# AirQualityMonitor.net
KiCad netlist of a schematic drawn in Altium Designer
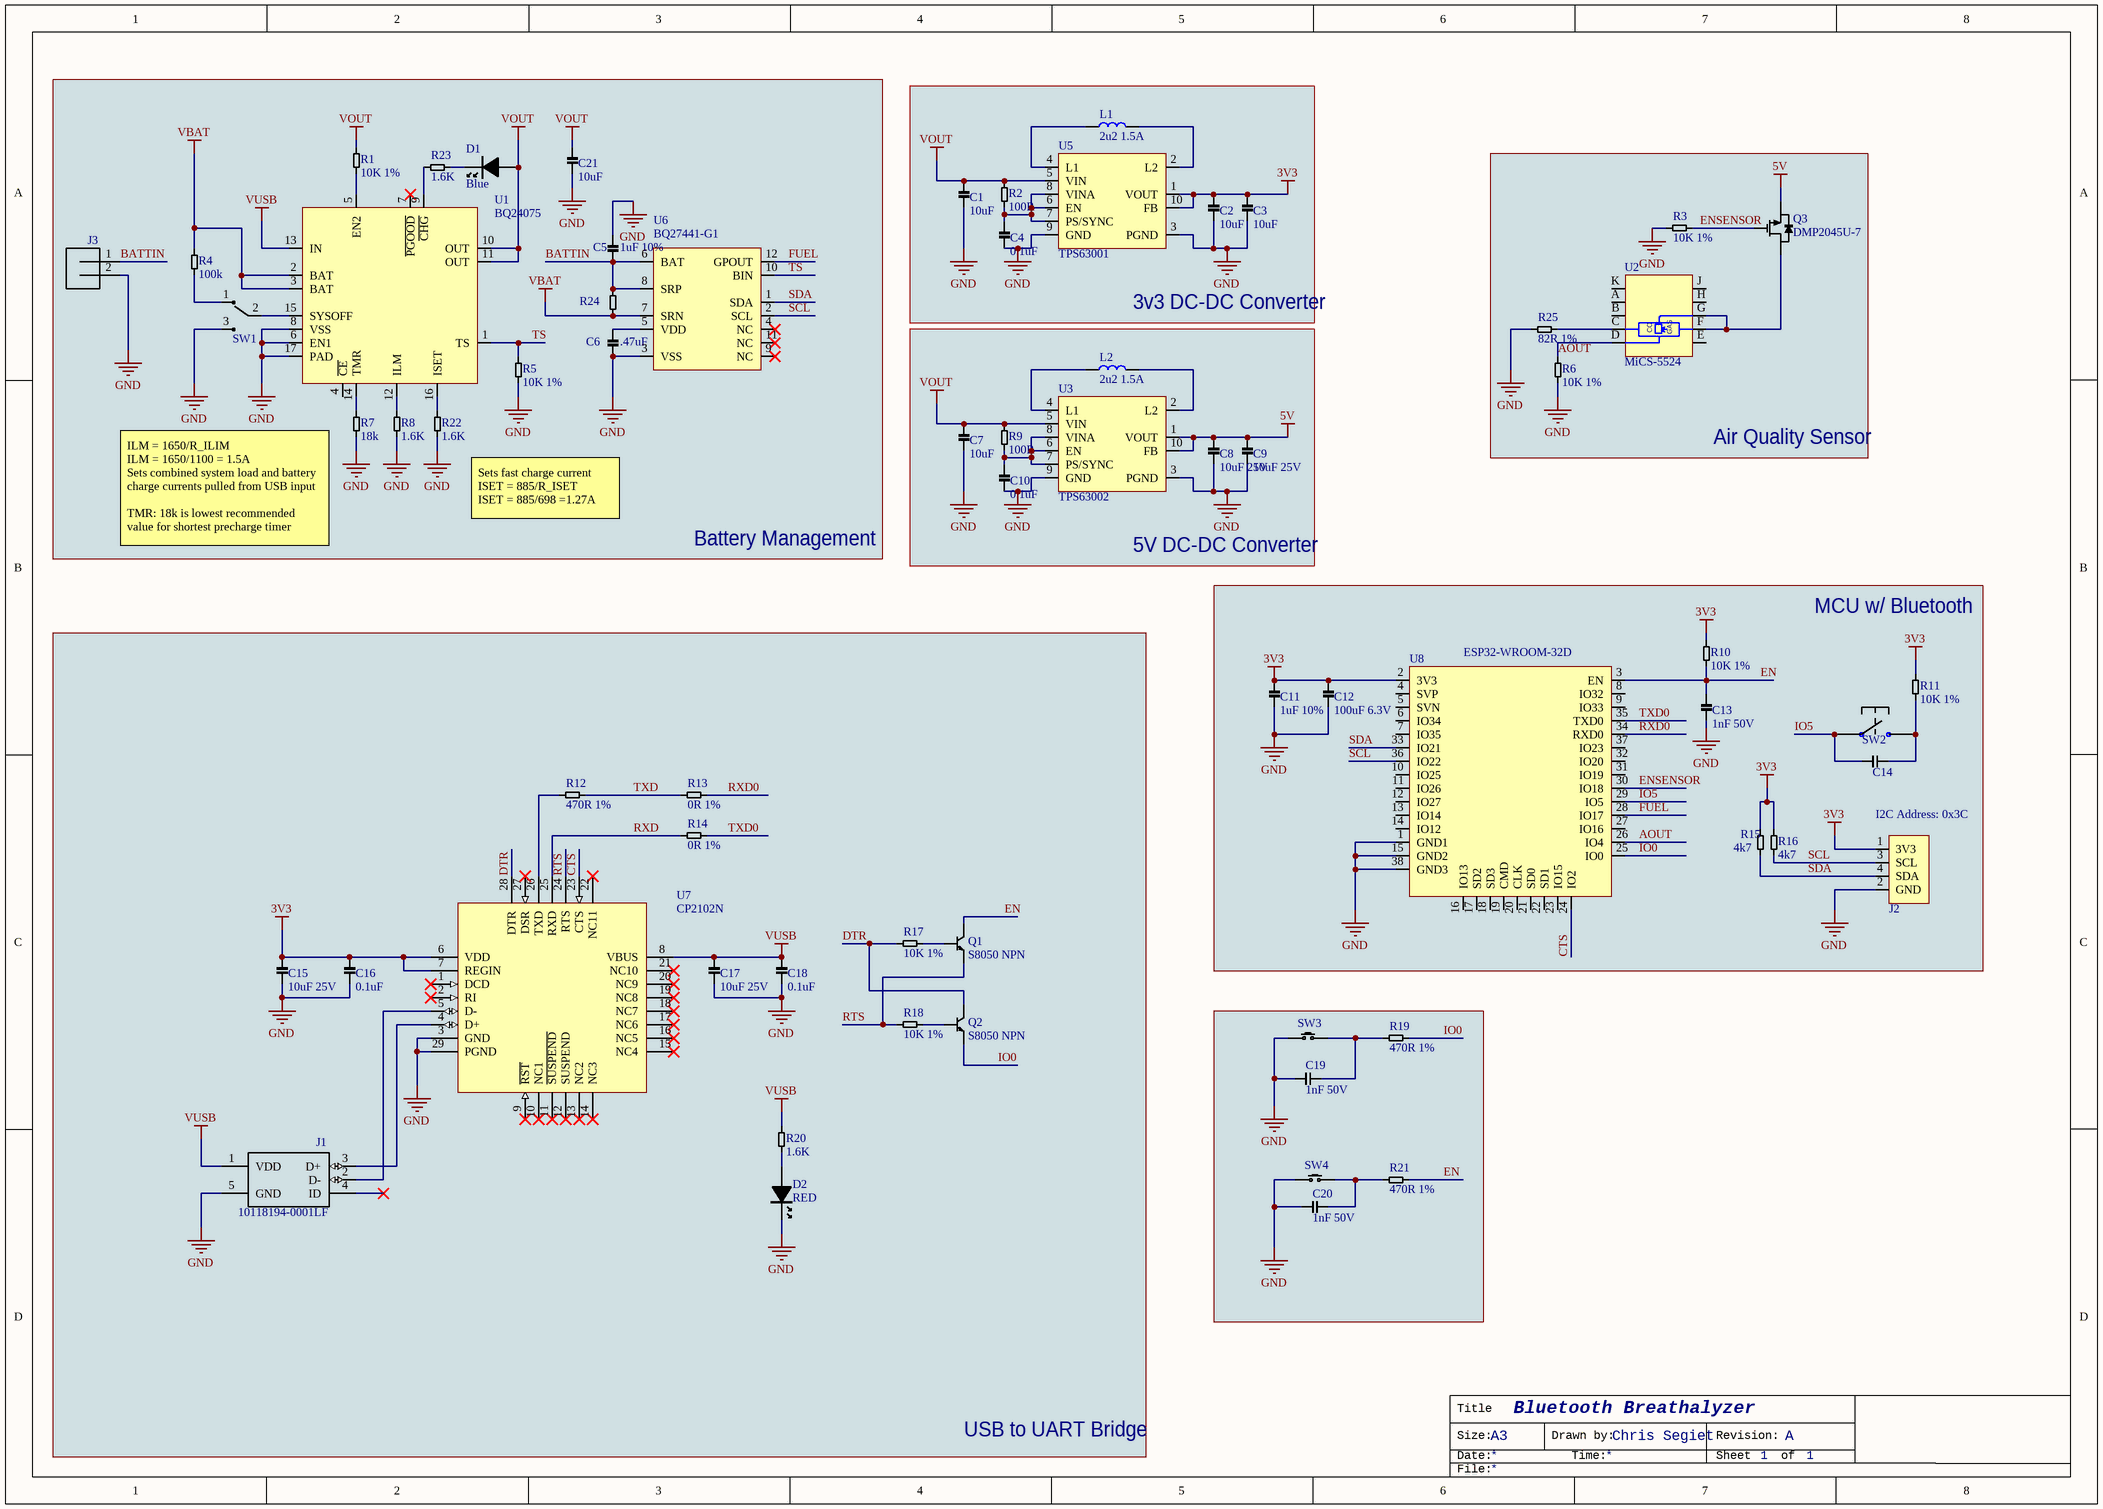
[diagram p0: AirQualityMonitor.SchDoc]

(export (version "E")
  (design (tool "Eeschema 10.0.6"))
  (components
    (comp (ref "C1")
      (value "10uF")
      (footprint "0805MLCC")
      (description "CAP CER 10UF 6.3V X7R 0805")
      (fields
        (field (name "MANUFACTURER") "Kyocera AVX")
        (field (name "MANUFACTURER PART NUMBER") "08056C106KAT2A")
      )
      (libsource (lib "Breathalyzer") (part "08056C106KAT2A"))
    )
    (comp (ref "C2")
      (value "10uF")
      (footprint "0805MLCC")
      (description "CAP CER 10UF 6.3V X7R 0805")
      (fields
        (field (name "MANUFACTURER") "Kyocera AVX")
        (field (name "MANUFACTURER PART NUMBER") "08056C106KAT2A")
      )
      (libsource (lib "") (part "08056C106KAT2A_1"))
    )
    (comp (ref "C3")
      (value "10uF")
      (footprint "0805MLCC")
      (description "CAP CER 10UF 6.3V X7R 0805")
      (fields
        (field (name "MANUFACTURER") "Kyocera AVX")
        (field (name "MANUFACTURER PART NUMBER") "08056C106KAT2A")
      )
      (libsource (lib "") (part "08056C106KAT2A_1"))
    )
    (comp (ref "C4")
      (value "0.1uF")
      (footprint "0603MLCC")
      (description "CAP CER 0.1UF 25V X7R 0603")
      (fields
        (field (name "MANUFACTURER") "Murata")
        (field (name "MANUFACTURER PART NUMBER") "GRM188R71E104KA01D")
      )
      (libsource (lib "Breathalyzer") (part "GRM188R71E104KA01D"))
    )
    (comp (ref "C5")
      (value "1uF 10%")
      (footprint "0603MLCC")
      (description "Multilayer Ceramic Capacitors MLCC - SMD/SMT 0603 1uF 10volts X5R 10%")
      (fields
        (field (name "MANUFACTURER") "Murata")
        (field (name "MANUFACTURER PART NUMBER") "GRM188R61A105KA61J")
      )
      (libsource (lib "Breathalyzer") (part "GRM188R61A105KA61J"))
    )
    (comp (ref "C6")
      (value ".47uF")
      (footprint "0805MLCC")
      (description "CAP CER 0.47UF 25V X7R 0805")
      (fields
        (field (name "MANUFACTURER") "Yageo")
        (field (name "MANUFACTURER PART NUMBER") "CC0805KKX7R8BB474")
      )
      (libsource (lib "Breathalyzer") (part "CC0805KKX7R8BB474"))
    )
    (comp (ref "C7")
      (value "10uF")
      (footprint "0805MLCC")
      (description "CAP CER 10UF 6.3V X7R 0805")
      (fields
        (field (name "MANUFACTURER") "Kyocera AVX")
        (field (name "MANUFACTURER PART NUMBER") "08056C106KAT2A")
      )
      (libsource (lib "Breathalyzer") (part "08056C106KAT2A"))
    )
    (comp (ref "C8")
      (value "10uF 25V")
      (footprint "1206MLCC")
      (description "CAP CER 10UF 25V X5R 1206")
      (fields
        (field (name "MANUFACTURER") "Taiyo Yuden")
        (field (name "MANUFACTURER PART NUMBER") "TMK316BJ106ML-T")
      )
      (libsource (lib "Breathalyzer") (part "TMK316BJ106ML-T"))
    )
    (comp (ref "C9")
      (value "10uF 25V")
      (footprint "1206MLCC")
      (description "CAP CER 10UF 25V X5R 1206")
      (fields
        (field (name "MANUFACTURER") "Taiyo Yuden")
        (field (name "MANUFACTURER PART NUMBER") "TMK316BJ106ML-T")
      )
      (libsource (lib "Breathalyzer") (part "TMK316BJ106ML-T"))
    )
    (comp (ref "C10")
      (value "0.1uF")
      (footprint "0603MLCC")
      (description "CAP CER 0.1UF 25V X7R 0603")
      (fields
        (field (name "MANUFACTURER") "Murata")
        (field (name "MANUFACTURER PART NUMBER") "GRM188R71E104KA01D")
      )
      (libsource (lib "Breathalyzer") (part "GRM188R71E104KA01D"))
    )
    (comp (ref "C11")
      (value "1uF 10%")
      (footprint "0603MLCC")
      (description "Multilayer Ceramic Capacitors MLCC - SMD/SMT 0603 1uF 10volts X5R 10%")
      (fields
        (field (name "MANUFACTURER") "Murata")
        (field (name "MANUFACTURER PART NUMBER") "GRM188R61A105KA61J")
      )
      (libsource (lib "Breathalyzer") (part "GRM188R61A105KA61J"))
    )
    (comp (ref "C12")
      (value "100uF 6.3V")
      (footprint "1206MLCC")
      (description "Multilayer Ceramic Capacitors MLCC - SMD/SMT 1206 100uF 6.3volt X5R +/-20%")
      (fields
        (field (name "MANUFACTURER") "Murata")
        (field (name "MANUFACTURER PART NUMBER") "GRM31CR60J107ME39K")
      )
      (libsource (lib "Breathalyzer") (part "GRM31CR60J107ME39K"))
    )
    (comp (ref "C13")
      (value "1nF 50V")
      (footprint "0603MLCC")
      (description "CAP CER 1000PF 50V 0603")
      (fields
        (field (name "MANUFACTURER") "Taiyo Yuden")
        (field (name "MANUFACTURER PART NUMBER") "UMK107SD102KA-T")
      )
      (libsource (lib "") (part "UMK107SD102KA-T_2"))
    )
    (comp (ref "C14")
      (value "1nF 50V")
      (footprint "0603MLCC")
      (description "CAP CER 1000PF 50V 0603")
      (fields
        (field (name "MANUFACTURER") "Taiyo Yuden")
        (field (name "MANUFACTURER PART NUMBER") "UMK107SD102KA-T")
      )
      (libsource (lib "Breathalyzer") (part "UMK107SD102KA-T"))
    )
    (comp (ref "C15")
      (value "10uF 25V")
      (footprint "1206MLCC")
      (description "CAP CER 10UF 25V X5R 1206")
      (fields
        (field (name "MANUFACTURER") "Taiyo Yuden")
        (field (name "MANUFACTURER PART NUMBER") "TMK316BJ106ML-T")
      )
      (libsource (lib "Breathalyzer") (part "TMK316BJ106ML-T"))
    )
    (comp (ref "C16")
      (value "0.1uF")
      (footprint "0603MLCC")
      (description "CAP CER 0.1UF 25V X7R 0603")
      (fields
        (field (name "MANUFACTURER") "Murata")
        (field (name "MANUFACTURER PART NUMBER") "GRM188R71E104KA01D")
      )
      (libsource (lib "Breathalyzer") (part "GRM188R71E104KA01D"))
    )
    (comp (ref "C17")
      (value "10uF 25V")
      (footprint "1206MLCC")
      (description "CAP CER 10UF 25V X5R 1206")
      (fields
        (field (name "MANUFACTURER") "Taiyo Yuden")
        (field (name "MANUFACTURER PART NUMBER") "TMK316BJ106ML-T")
      )
      (libsource (lib "Breathalyzer") (part "TMK316BJ106ML-T"))
    )
    (comp (ref "C18")
      (value "0.1uF")
      (footprint "0603MLCC")
      (description "CAP CER 0.1UF 25V X7R 0603")
      (fields
        (field (name "MANUFACTURER") "Murata")
        (field (name "MANUFACTURER PART NUMBER") "GRM188R71E104KA01D")
      )
      (libsource (lib "Breathalyzer") (part "GRM188R71E104KA01D"))
    )
    (comp (ref "C19")
      (value "1nF 50V")
      (footprint "0603MLCC")
      (description "CAP CER 1000PF 50V 0603")
      (fields
        (field (name "MANUFACTURER") "Taiyo Yuden")
        (field (name "MANUFACTURER PART NUMBER") "UMK107SD102KA-T")
      )
      (libsource (lib "") (part "UMK107SD102KA-T_1"))
    )
    (comp (ref "C20")
      (value "1nF 50V")
      (footprint "0603MLCC")
      (description "CAP CER 1000PF 50V 0603")
      (fields
        (field (name "MANUFACTURER") "Taiyo Yuden")
        (field (name "MANUFACTURER PART NUMBER") "UMK107SD102KA-T")
      )
      (libsource (lib "") (part "UMK107SD102KA-T_1"))
    )
    (comp (ref "C21")
      (value "10uF")
      (footprint "0805MLCC")
      (description "CAP CER 10UF 6.3V X7R 0805")
      (fields
        (field (name "MANUFACTURER") "Kyocera AVX")
        (field (name "MANUFACTURER PART NUMBER") "08056C106KAT2A")
      )
      (libsource (lib "Breathalyzer") (part "08056C106KAT2A"))
    )
    (comp (ref "D1")
      (value "Blue")
      (footprint "LTST-C193TBKT-5A")
      (description "Standard LEDs - SMD Blue 470nm 28mcd 5mA")
      (fields
        (field (name "MANUFACTURER") "Vishay Lite-On")
        (field (name "MANUFACTURER PART NUMBER") "LTST-C193TBKT-5A")
      )
      (libsource (lib "Breathalyzer") (part "LTST-C193TBKT-5A"))
    )
    (comp (ref "D2")
      (value "RED")
      (footprint "LEDC2012X75N_APT2012SRCPRV(Primary)")
      (description "LED 2X1.2MM 640NM RD WTR CLR SMD")
      (fields
        (field (name "MANUFACTURER") "Kingbright")
        (field (name "MANUFACTURER PART NUMBER") "APT2012SRCPRV")
      )
      (libsource (lib "Breathalyzer") (part "APT2012SRCPRV"))
    )
    (comp (ref "J1")
      (value "10118194-0001LF")
      (footprint "FRAMATOME_10118194-0001LF")
      (description "Conn Micro USB Type B RCP 5 POS 0.65mm Solder RA SMD 5 Terminal 1 Port T/R")
      (fields (field (name "MF") "Amphenol FCI"))
      (libsource (lib "Breathalyzer") (part "10118194-0001LF"))
    )
    (comp (ref "J2")
      (value "Header for I2C Testing")
      (footprint "1x4 Header 2.54mm pitch")
      (description "1x4 Header for I2C Testing")
      (libsource (lib "Breathalyzer") (part "I2C Testing"))
    )
    (comp (ref "J3")
      (value "S2B-PH-SM4-TB")
      (footprint "JST_S2B-PH-SM4-TB")
      (description "Socket; wire-board; male; PIN: 2; 2mm; SMT; PH; 100V; 2A; -25Ã·85Â°C")
      (fields (field (name "MF") "JST"))
      (libsource (lib "Breathalyzer") (part "S2B-PH-SM4-TB"))
    )
    (comp (ref "L1")
      (value "2u2 1.5A")
      (footprint "VLF4012AT-2R2M1R5")
      (description "FIXED IND 2.2UH 1.5A 87 MOHM SMD")
      (fields
        (field (name "MANUFACTURER") "TDK")
        (field (name "MANUFACTURER PART NUMBER") "VLF4012AT-2R2M1R5")
      )
      (libsource (lib "Breathalyzer") (part "VLF4012AT-2R2M1R5"))
    )
    (comp (ref "L2")
      (value "2u2 1.5A")
      (footprint "VLF4012AT-2R2M1R5")
      (description "FIXED IND 2.2UH 1.5A 87 MOHM SMD")
      (fields
        (field (name "MANUFACTURER") "TDK")
        (field (name "MANUFACTURER PART NUMBER") "VLF4012AT-2R2M1R5")
      )
      (libsource (lib "Breathalyzer") (part "VLF4012AT-2R2M1R5"))
    )
    (comp (ref "Q1")
      (value "S8050 NPN")
      (footprint "SOT23-NPN")
      (description "TRANS NPN 25V 1.5A SOT-23")
      (fields (field (name "MANUFACTURER") "MCC") (field (name "MANUFACTURER PART NUMBER") "MMSS8050-L-TP"))
      (libsource (lib "Breathalyzer") (part "MMSS8050-L-TP"))
    )
    (comp (ref "Q2")
      (value "S8050 NPN")
      (footprint "SOT23-NPN")
      (description "TRANS NPN 25V 1.5A SOT-23")
      (fields (field (name "MANUFACTURER") "MCC") (field (name "MANUFACTURER PART NUMBER") "MMSS8050-L-TP"))
      (libsource (lib "Breathalyzer") (part "MMSS8050-L-TP"))
    )
    (comp (ref "Q3")
      (value "DMP2045U-7")
      (footprint "SOT91P240X110-3N")
      (description "P-Channel MOSFET 045R at VGS=-4.5V ID = -4.3A")
      (fields (field (name "MANUFACTURER") "Diodes"))
      (libsource (lib "Breathalyzer") (part "DMP2045U-7"))
    )
    (comp (ref "R1")
      (value "10K 1%")
      (footprint "0805RES")
      (description "RES SMD 10K OHM 1% 1/8W 0805")
      (fields
        (field (name "MANUFACTURER") "Yageo")
        (field (name "MANUFACTURER PART NUMBER") "RC0805FR-0710KL")
      )
      (libsource (lib "") (part "RC0805FR-0710KL_1"))
    )
    (comp (ref "R2")
      (value "100R")
      (footprint "0805RES")
      (description "RES, THICK FILM, 100R, 5%, 0.125W, 0805")
      (fields
        (field (name "MANUFACTURER") "Yageo")
        (field (name "MANUFACTURER PART NUMBER") "RC0805JR-07100RL")
      )
      (libsource (lib "Breathalyzer") (part "RC0805JR-07100RL"))
    )
    (comp (ref "R3")
      (value "10K 1%")
      (footprint "0805RES")
      (description "RES SMD 10K OHM 1% 1/8W 0805")
      (fields
        (field (name "MANUFACTURER") "Yageo")
        (field (name "MANUFACTURER PART NUMBER") "RC0805FR-0710KL")
      )
      (libsource (lib "") (part "RC0805FR-0710KL_2"))
    )
    (comp (ref "R4")
      (value "100k")
      (footprint "0603RES")
      (description "YAGEO         RC0603FR-07100KL             RES, THICK FILM, 100K, 1%, 0.1W, 0603")
      (fields
        (field (name "MANUFACTURER") "Yageo")
        (field (name "MANUFACTURER PART NUMBER") "RC0603FR-07100KL")
      )
      (libsource (lib "Breathalyzer") (part "RC0603FR-07100KL"))
    )
    (comp (ref "R5")
      (value "10K 1%")
      (footprint "0805RES")
      (description "RES SMD 10K OHM 1% 1/8W 0805")
      (fields
        (field (name "MANUFACTURER") "Yageo")
        (field (name "MANUFACTURER PART NUMBER") "RC0805FR-0710KL")
      )
      (libsource (lib "") (part "RC0805FR-0710KL_1"))
    )
    (comp (ref "R6")
      (value "10K 1%")
      (footprint "0805RES")
      (description "RES SMD 10K OHM 1% 1/8W 0805")
      (fields
        (field (name "MANUFACTURER") "Yageo")
        (field (name "MANUFACTURER PART NUMBER") "RC0805FR-0710KL")
      )
      (libsource (lib "") (part "RC0805FR-0710KL_1"))
    )
    (comp (ref "R7")
      (value "18k")
      (footprint "0805RES")
      (description "RES SMD 18K OHM 1% 1/8W 0805")
      (fields
        (field (name "MANUFACTURER") "Vishay")
        (field (name "MANUFACTURER PART NUMBER") "CRCW080518K0FKEA")
      )
      (libsource (lib "Breathalyzer") (part "CRCW080518K0FKEA"))
    )
    (comp (ref "R8")
      (value "1.6K")
      (footprint "0805RES")
      (description "RES SMD 1.6K OHM 1% 1/8W 0805")
      (fields
        (field (name "MANUFACTURER") "Vishay")
        (field (name "MANUFACTURER PART NUMBER") "CRCW08051K60FKEA")
      )
      (libsource (lib "Breathalyzer") (part "CRCW08051K60FKEA"))
    )
    (comp (ref "R9")
      (value "100R")
      (footprint "0805RES")
      (description "RES, THICK FILM, 100R, 5%, 0.125W, 0805")
      (fields
        (field (name "MANUFACTURER") "Yageo")
        (field (name "MANUFACTURER PART NUMBER") "RC0805JR-07100RL")
      )
      (libsource (lib "Breathalyzer") (part "RC0805JR-07100RL"))
    )
    (comp (ref "R10")
      (value "10K 1%")
      (footprint "0805RES")
      (description "RES SMD 10K OHM 1% 1/8W 0805")
      (fields
        (field (name "MANUFACTURER") "Yageo")
        (field (name "MANUFACTURER PART NUMBER") "RC0805FR-0710KL")
      )
      (libsource (lib "") (part "RC0805FR-0710KL_1"))
    )
    (comp (ref "R11")
      (value "10K 1%")
      (footprint "0805RES")
      (description "RES SMD 10K OHM 1% 1/8W 0805")
      (fields
        (field (name "MANUFACTURER") "Yageo")
        (field (name "MANUFACTURER PART NUMBER") "RC0805FR-0710KL")
      )
      (libsource (lib "") (part "RC0805FR-0710KL_1"))
    )
    (comp (ref "R12")
      (value "470R 1%")
      (footprint "0805RES")
      (description "RES SMD 470 OHM 1% 1/8W 0805")
      (fields
        (field (name "MANUFACTURER") "Yageo")
        (field (name "MANUFACTURER PART NUMBER") "RC0805FR-07470RL")
      )
      (libsource (lib "Breathalyzer") (part "RC0805FR-07470RL"))
    )
    (comp (ref "R13")
      (value "0R 1%")
      (footprint "0603RES")
      (description "Thick Film Resistors - SMD 0.0ohm 1%")
      (fields
        (field (name "MANUFACTURER") "Yageo")
        (field (name "MANUFACTURER PART NUMBER") "RC0603FR-070RL")
      )
      (libsource (lib "Breathalyzer") (part "RC0603FR-070RL"))
    )
    (comp (ref "R14")
      (value "0R 1%")
      (footprint "0603RES")
      (description "Thick Film Resistors - SMD 0.0ohm 1%")
      (fields
        (field (name "MANUFACTURER") "Yageo")
        (field (name "MANUFACTURER PART NUMBER") "RC0603FR-070RL")
      )
      (libsource (lib "Breathalyzer") (part "RC0603FR-070RL"))
    )
    (comp (ref "R15")
      (value "4k7")
      (footprint "0805RES")
      (description "YAGEO         RC0805JR-074K7L             RES, THICK FILM, 4K7, 5%, 0.125W, 0805")
      (fields
        (field (name "MANUFACTURER") "Yageo")
        (field (name "MANUFACTURER PART NUMBER") "RC0805JR-074K7L")
      )
      (libsource (lib "") (part "RC0805JR-074K7L_1"))
    )
    (comp (ref "R16")
      (value "4k7")
      (footprint "0805RES")
      (description "YAGEO         RC0805JR-074K7L             RES, THICK FILM, 4K7, 5%, 0.125W, 0805")
      (fields
        (field (name "MANUFACTURER") "Yageo")
        (field (name "MANUFACTURER PART NUMBER") "RC0805JR-074K7L")
      )
      (libsource (lib "Breathalyzer") (part "RC0805JR-074K7L"))
    )
    (comp (ref "R17")
      (value "10K 1%")
      (footprint "0805RES")
      (description "RES SMD 10K OHM 1% 1/8W 0805")
      (fields
        (field (name "MANUFACTURER") "Yageo")
        (field (name "MANUFACTURER PART NUMBER") "RC0805FR-0710KL")
      )
      (libsource (lib "Breathalyzer") (part "RC0805FR-0710KL"))
    )
    (comp (ref "R18")
      (value "10K 1%")
      (footprint "0805RES")
      (description "RES SMD 10K OHM 1% 1/8W 0805")
      (fields
        (field (name "MANUFACTURER") "Yageo")
        (field (name "MANUFACTURER PART NUMBER") "RC0805FR-0710KL")
      )
      (libsource (lib "Breathalyzer") (part "RC0805FR-0710KL"))
    )
    (comp (ref "R19")
      (value "470R 1%")
      (footprint "0805RES")
      (description "RES SMD 470 OHM 1% 1/8W 0805")
      (fields
        (field (name "MANUFACTURER") "Yageo")
        (field (name "MANUFACTURER PART NUMBER") "RC0805FR-07470RL")
      )
      (libsource (lib "Breathalyzer") (part "RC0805FR-07470RL"))
    )
    (comp (ref "R20")
      (value "1.6K")
      (footprint "0805RES")
      (description "RES SMD 1.6K OHM 1% 1/8W 0805")
      (fields
        (field (name "MANUFACTURER") "Vishay")
        (field (name "MANUFACTURER PART NUMBER") "CRCW08051K60FKEA")
      )
      (libsource (lib "Breathalyzer") (part "CRCW08051K60FKEA"))
    )
    (comp (ref "R21")
      (value "470R 1%")
      (footprint "0805RES")
      (description "RES SMD 470 OHM 1% 1/8W 0805")
      (fields
        (field (name "MANUFACTURER") "Yageo")
        (field (name "MANUFACTURER PART NUMBER") "RC0805FR-07470RL")
      )
      (libsource (lib "Breathalyzer") (part "RC0805FR-07470RL"))
    )
    (comp (ref "R22")
      (value "1.6K")
      (footprint "0805RES")
      (description "RES SMD 1.6K OHM 1% 1/8W 0805")
      (fields
        (field (name "MANUFACTURER") "Vishay")
        (field (name "MANUFACTURER PART NUMBER") "CRCW08051K60FKEA")
      )
      (libsource (lib "Breathalyzer") (part "CRCW08051K60FKEA"))
    )
    (comp (ref "R23")
      (value "1.6K")
      (footprint "0805RES")
      (description "RES SMD 1.6K OHM 1% 1/8W 0805")
      (fields
        (field (name "MANUFACTURER") "Vishay")
        (field (name "MANUFACTURER PART NUMBER") "CRCW08051K60FKEA")
      )
      (libsource (lib "") (part "CRCW08051K60FKEA_1"))
    )
    (comp (ref "R24")
      (value "0.01R 1% 1W")
      (footprint "1206RES")
      (description "Current Sense Resistor, 0.01 ohm, 1206 [3216 Metric], 1 W,  1%, ERJ8B Series")
      (fields
        (field (name "MANUFACTURER") "Panasonic")
        (field (name "MANUFACTURER PART NUMBER") "ERJ-8BWFR010V")
      )
      (libsource (lib "Breathalyzer") (part "ERJ-8BWFR010V"))
    )
    (comp (ref "R25")
      (value "82R 1%")
      (footprint "0805RES")
      (description "RES SMD 82 OHM 1% 1/8W 0805")
      (fields
        (field (name "MANUFACTURER") "Vishay")
        (field (name "MANUFACTURER PART NUMBER") "CRCW080582R0FKEA")
      )
      (libsource (lib "Breathalyzer") (part "CRCW080582R0FKEA"))
    )
    (comp (ref "SW1")
      (value "PCM12SMTR")
      (footprint "SW_PCM12SMTR_PCM12SMTR(Primary)")
      (description "C & K COMPONENTS         PCM12SMTR             Slide Switch, SPDT, On-On, SMD, PCM Series, 300 mA")
      (fields (field (name "MANUFACTURER") "ITT C&K"))
      (libsource (lib "Breathalyzer") (part "PCM12SMTR"))
    )
    (comp (ref "SW2")
      (value "PTS645SM43SMTR")
      (footprint "PTS645SM43SMTR")
      (description "Switch Tact 6mm 100gf h=4.3mm")
      (fields (field (name "MF") "C&K"))
      (libsource (lib "Breathalyzer") (part "PTS645SM43SMTR"))
    )
    (comp (ref "SW3")
      (value "SMD Light Touch Switch")
      (footprint "Tactile Switch")
      (description "Tactile Switch")
      (fields (field (name "MANUFACTURER") "Panasonic") (field (name "MANUFACTURER PART NUMBER") "EVPAWCD4A"))
      (libsource (lib "Breathalyzer") (part "EVPAWCD4A"))
    )
    (comp (ref "SW4")
      (value "SMD Light Touch Switch")
      (footprint "Tactile Switch")
      (description "Tactile Switch")
      (fields (field (name "MANUFACTURER") "Panasonic") (field (name "MANUFACTURER PART NUMBER") "EVPAWCD4A"))
      (libsource (lib "Breathalyzer") (part "EVPAWCD4A"))
    )
    (comp (ref "U1")
      (value "BQ24075")
      (footprint "VQFN 16-pin 0.5mm pitch")
      (description "TEXAS INSTRUMENTS   BQ24075RGTT   IC, BATTERY CHARGER,LI-ION, 1.5A, QFN-16")
      (fields
        (field (name "MANUFACTURER") "Texas Instruments")
        (field (name "MANUFACTURER PART NUMBER") "BQ24075RGTT")
      )
      (libsource (lib "Breathalyzer") (part "BQ24075RGTT"))
    )
    (comp (ref "U2")
      (value "MiCS-5524")
      (footprint "MiCS5524 Ethanol Sensor")
      (description "10-500ppm Ethanol Sensor")
      (fields (field (name "MANUFACTURER") "Amphenol SGX Sensortech"))
      (libsource (lib "Breathalyzer") (part "MiCS-5524"))
    )
    (comp (ref "U3")
      (value "TPS63002")
      (footprint "SON50P300X300X100-11N")
      (description "IC REG BUCK BOOST 5V 1.6A 10SON")
      (fields
        (field (name "MANUFACTURER") "Texas Instruments")
        (field (name "MANUFACTURER PART NUMBER") "TPS63002DRCR")
      )
      (libsource (lib "Breathalyzer") (part "TPS63002DRCR"))
    )
    (comp (ref "U5")
      (value "TPS63001")
      (footprint "SON50P300X300X100-11N")
      (description "Conv DC-DC Single Non-Inv/Inv/Step Up/Step Down 1.8V to 5.5V 10-Pin VSON EP T/R")
      (fields
        (field (name "MANUFACTURER") "Texas Instruments")
        (field (name "MANUFACTURER PART NUMBER") "TPS63001DRCT")
      )
      (libsource (lib "Breathalyzer") (part "TPS63001DRCT"))
    )
    (comp (ref "U6")
      (value "BQ27441-G1")
      (footprint "SON40P400X250X100-13N")
      (description "IC BATT FUEL GAUGE LI-ION 12SON")
      (fields
        (field (name "MANUFACTURER") "Texas Instruments")
        (field (name "MANUFACTURER PART NUMBER") "BQ27441DRZR-G1A")
      )
      (libsource (lib "Breathalyzer") (part "BQ27441DRZR-G1A"))
    )
    (comp (ref "U7")
      (value "CP2102N")
      (footprint "QFN50P500X500X80-29N")
      (fields
        (field (name "MANUFACTURER") "Silicon Labs")
        (field (name "MANUFACTURER PART NUMBER") "CP2102N-A01-GQFN28")
      )
      (libsource (lib "Breathalyzer") (part "CP2102N-A01-GQFN28"))
    )
    (comp (ref "U8")
      (value "ESP32-WROOM-32D")
      (footprint "MODULE_ESP32-WROOM-32D")
      (description "ESP32 Module")
      (fields (field (name "MANUFACTURER") "Espressif Systems"))
      (libsource (lib "Breathalyzer") (part "ESP32-WROOM-32D"))
    )
  )
  (nets
    (net (code "1") (name "/AOUT") (class "Default")
      (node (ref "R6") (pin "2") (pinfunction "2_2") (pintype "passive"))
      (node (ref "U2") (pin "D") (pinfunction "D_D") (pintype "passive"))
      (node (ref "U8") (pin "26") (pinfunction "IO4_26") (pintype "bidirectional"))
    )
    (net (code "2") (name "/BATTIN") (class "Default")
      (node (ref "C5") (pin "1") (pinfunction "1_1") (pintype "passive"))
      (node (ref "J3") (pin "1") (pinfunction "1_1") (pintype "passive"))
      (node (ref "R24") (pin "2") (pinfunction "2_2") (pintype "passive"))
      (node (ref "U6") (pin "6") (pinfunction "BAT_6") (pintype "passive"))
      (node (ref "U6") (pin "8") (pinfunction "SRP_8") (pintype "passive"))
    )
    (net (code "3") (name "/CTS") (class "Default")
      (node (ref "U7") (pin "23") (pinfunction "CTS_23") (pintype "input"))
      (node (ref "U8") (pin "24") (pinfunction "IO2_24") (pintype "bidirectional"))
    )
    (net (code "4") (name "/DTR") (class "Default")
      (node (ref "Q2") (pin "C") (pinfunction "C_C") (pintype "passive"))
      (node (ref "R17") (pin "1") (pinfunction "1_1") (pintype "passive"))
      (node (ref "U7") (pin "28") (pinfunction "DTR_28") (pintype "passive"))
    )
    (net (code "5") (name "/EN") (class "Default")
      (node (ref "C13") (pin "2") (pinfunction "2_2") (pintype "passive"))
      (node (ref "Q1") (pin "C") (pinfunction "C_C") (pintype "passive"))
      (node (ref "R10") (pin "1") (pinfunction "1_1") (pintype "passive"))
      (node (ref "R21") (pin "2") (pinfunction "2_2") (pintype "passive"))
      (node (ref "U8") (pin "3") (pinfunction "EN_3") (pintype "passive"))
    )
    (net (code "6") (name "/ENSENSOR") (class "Default")
      (node (ref "Q3") (pin "G") (pinfunction "G_G") (pintype "passive"))
      (node (ref "R3") (pin "1") (pinfunction "1_1") (pintype "passive"))
      (node (ref "U8") (pin "30") (pinfunction "IO18_30") (pintype "bidirectional"))
    )
    (net (code "7") (name "/FUEL") (class "Default")
      (node (ref "U6") (pin "12") (pinfunction "GPOUT_12") (pintype "passive"))
      (node (ref "U8") (pin "28") (pinfunction "IO17_28") (pintype "bidirectional"))
    )
    (net (code "8") (name "/IO0") (class "Default")
      (node (ref "Q2") (pin "E") (pinfunction "E_E") (pintype "passive"))
      (node (ref "R19") (pin "2") (pinfunction "2_2") (pintype "passive"))
      (node (ref "U8") (pin "25") (pinfunction "IO0_25") (pintype "bidirectional"))
    )
    (net (code "9") (name "/IO5") (class "Default")
      (node (ref "C14") (pin "2") (pinfunction "2_2") (pintype "passive"))
      (node (ref "SW2") (pin "1") (pinfunction "P$1_1") (pintype "passive"))
      (node (ref "SW2") (pin "2") (pinfunction "P$1_2") (pintype "passive"))
      (node (ref "U8") (pin "29") (pinfunction "IO5_29") (pintype "bidirectional"))
    )
    (net (code "10") (name "/RTS") (class "Default")
      (node (ref "Q1") (pin "E") (pinfunction "E_E") (pintype "passive"))
      (node (ref "R18") (pin "1") (pinfunction "1_1") (pintype "passive"))
      (node (ref "U7") (pin "24") (pinfunction "RTS_24") (pintype "passive"))
    )
    (net (code "11") (name "/RXD") (class "Default")
      (node (ref "R14") (pin "1") (pinfunction "1_1") (pintype "passive"))
      (node (ref "U7") (pin "25") (pinfunction "RXD_25") (pintype "passive"))
    )
    (net (code "12") (name "/RXD0") (class "Default")
      (node (ref "R13") (pin "2") (pinfunction "2_2") (pintype "passive"))
      (node (ref "U8") (pin "34") (pinfunction "RXD0_34") (pintype "bidirectional"))
    )
    (net (code "13") (name "/SCL") (class "Default")
      (node (ref "J2") (pin "3") (pinfunction "SCL_3") (pintype "passive"))
      (node (ref "R16") (pin "1") (pinfunction "1_1") (pintype "passive"))
      (node (ref "U6") (pin "2") (pinfunction "SCL_2") (pintype "passive"))
      (node (ref "U8") (pin "36") (pinfunction "IO22_36") (pintype "bidirectional"))
    )
    (net (code "14") (name "/SDA") (class "Default")
      (node (ref "J2") (pin "4") (pinfunction "SDA_4") (pintype "passive"))
      (node (ref "R15") (pin "2") (pinfunction "2_2") (pintype "passive"))
      (node (ref "U6") (pin "1") (pinfunction "SDA_1") (pintype "passive"))
      (node (ref "U8") (pin "33") (pinfunction "IO21_33") (pintype "bidirectional"))
    )
    (net (code "15") (name "/TS") (class "Default")
      (node (ref "R5") (pin "2") (pinfunction "2_2") (pintype "passive"))
      (node (ref "U1") (pin "1") (pinfunction "TS_1") (pintype "passive"))
      (node (ref "U6") (pin "10") (pinfunction "BIN_10") (pintype "passive"))
    )
    (net (code "16") (name "/TXD") (class "Default")
      (node (ref "R12") (pin "2") (pinfunction "2_2") (pintype "passive"))
      (node (ref "R13") (pin "1") (pinfunction "1_1") (pintype "passive"))
    )
    (net (code "17") (name "/TXD0") (class "Default")
      (node (ref "R14") (pin "2") (pinfunction "2_2") (pintype "passive"))
      (node (ref "U8") (pin "35") (pinfunction "TXD0_35") (pintype "bidirectional"))
    )
    (net (code "18") (name "3V3") (class "Default")
      (node (ref "C11") (pin "2") (pinfunction "2_2") (pintype "passive"))
      (node (ref "C12") (pin "2") (pinfunction "2_2") (pintype "passive"))
      (node (ref "C15") (pin "2") (pinfunction "2_2") (pintype "passive"))
      (node (ref "C16") (pin "2") (pinfunction "2_2") (pintype "passive"))
      (node (ref "C2") (pin "2") (pinfunction "2_2") (pintype "passive"))
      (node (ref "C3") (pin "2") (pinfunction "2_2") (pintype "passive"))
      (node (ref "J2") (pin "1") (pinfunction "3V3_1") (pintype "passive"))
      (node (ref "R10") (pin "2") (pinfunction "2_2") (pintype "passive"))
      (node (ref "R11") (pin "2") (pinfunction "2_2") (pintype "passive"))
      (node (ref "R15") (pin "1") (pinfunction "1_1") (pintype "passive"))
      (node (ref "R16") (pin "2") (pinfunction "2_2") (pintype "passive"))
      (node (ref "U5") (pin "1") (pinfunction "VOUT_1") (pintype "passive"))
      (node (ref "U5") (pin "10") (pinfunction "FB_10") (pintype "passive"))
      (node (ref "U7") (pin "6") (pinfunction "VDD_6") (pintype "passive"))
      (node (ref "U7") (pin "7") (pinfunction "REGIN_7") (pintype "passive"))
      (node (ref "U8") (pin "2") (pinfunction "3V3_2") (pintype "passive"))
    )
    (net (code "19") (name "5V") (class "Default")
      (node (ref "C8") (pin "2") (pinfunction "2_2") (pintype "passive"))
      (node (ref "C9") (pin "2") (pinfunction "2_2") (pintype "passive"))
      (node (ref "Q3") (pin "S") (pinfunction "S_S") (pintype "passive"))
      (node (ref "U3") (pin "1") (pinfunction "VOUT_1") (pintype "passive"))
      (node (ref "U3") (pin "10") (pinfunction "FB_10") (pintype "passive"))
    )
    (net (code "20") (name "GND") (class "Default")
      (node (ref "C1") (pin "2") (pinfunction "2_2") (pintype "passive"))
      (node (ref "C10") (pin "1") (pinfunction "1_1") (pintype "passive"))
      (node (ref "C11") (pin "1") (pinfunction "1_1") (pintype "passive"))
      (node (ref "C12") (pin "1") (pinfunction "1_1") (pintype "passive"))
      (node (ref "C13") (pin "1") (pinfunction "1_1") (pintype "passive"))
      (node (ref "C15") (pin "1") (pinfunction "1_1") (pintype "passive"))
      (node (ref "C16") (pin "1") (pinfunction "1_1") (pintype "passive"))
      (node (ref "C17") (pin "1") (pinfunction "1_1") (pintype "passive"))
      (node (ref "C18") (pin "1") (pinfunction "1_1") (pintype "passive"))
      (node (ref "C19") (pin "1") (pinfunction "1_1") (pintype "passive"))
      (node (ref "C2") (pin "1") (pinfunction "1_1") (pintype "passive"))
      (node (ref "C20") (pin "1") (pinfunction "1_1") (pintype "passive"))
      (node (ref "C21") (pin "2") (pinfunction "2_2") (pintype "passive"))
      (node (ref "C3") (pin "1") (pinfunction "1_1") (pintype "passive"))
      (node (ref "C4") (pin "1") (pinfunction "1_1") (pintype "passive"))
      (node (ref "C5") (pin "2") (pinfunction "2_2") (pintype "passive"))
      (node (ref "C6") (pin "1") (pinfunction "1_1") (pintype "passive"))
      (node (ref "C7") (pin "2") (pinfunction "2_2") (pintype "passive"))
      (node (ref "C8") (pin "1") (pinfunction "1_1") (pintype "passive"))
      (node (ref "C9") (pin "1") (pinfunction "1_1") (pintype "passive"))
      (node (ref "D2") (pin "2") (pinfunction "2_2") (pintype "passive"))
      (node (ref "J1") (pin "5") (pinfunction "GND_5") (pintype "power_in"))
      (node (ref "J2") (pin "2") (pinfunction "GND_2") (pintype "passive"))
      (node (ref "J3") (pin "2") (pinfunction "2_2") (pintype "passive"))
      (node (ref "R22") (pin "1") (pinfunction "1_1") (pintype "passive"))
      (node (ref "R25") (pin "1") (pinfunction "1_1") (pintype "passive"))
      (node (ref "R3") (pin "2") (pinfunction "2_2") (pintype "passive"))
      (node (ref "R5") (pin "1") (pinfunction "1_1") (pintype "passive"))
      (node (ref "R6") (pin "1") (pinfunction "1_1") (pintype "passive"))
      (node (ref "R7") (pin "1") (pinfunction "1_1") (pintype "passive"))
      (node (ref "R8") (pin "1") (pinfunction "1_1") (pintype "passive"))
      (node (ref "SW1") (pin "3") (pinfunction "3_3") (pintype "passive"))
      (node (ref "SW3") (pin "1") (pinfunction "1_1") (pintype "passive"))
      (node (ref "SW4") (pin "1") (pinfunction "1_1") (pintype "passive"))
      (node (ref "U1") (pin "17") (pinfunction "PAD_17") (pintype "passive"))
      (node (ref "U1") (pin "6") (pinfunction "EN1_6") (pintype "passive"))
      (node (ref "U1") (pin "8") (pinfunction "VSS_8") (pintype "passive"))
      (node (ref "U3") (pin "3") (pinfunction "PGND_3") (pintype "passive"))
      (node (ref "U3") (pin "9") (pinfunction "GND_9") (pintype "passive"))
      (node (ref "U5") (pin "3") (pinfunction "PGND_3") (pintype "passive"))
      (node (ref "U5") (pin "9") (pinfunction "GND_9") (pintype "passive"))
      (node (ref "U6") (pin "3") (pinfunction "VSS_3") (pintype "passive"))
      (node (ref "U7") (pin "29") (pinfunction "PGND_29") (pintype "passive"))
      (node (ref "U7") (pin "3") (pinfunction "GND_3") (pintype "passive"))
      (node (ref "U8") (pin "1") (pinfunction "GND1_1") (pintype "passive"))
      (node (ref "U8") (pin "15") (pinfunction "GND2_15") (pintype "passive"))
      (node (ref "U8") (pin "38") (pinfunction "GND3_38") (pintype "passive"))
    )
    (net (code "21") (name "Net-(C14-Pad1)") (class "Default")
      (node (ref "C14") (pin "1") (pinfunction "1_1") (pintype "passive"))
      (node (ref "R11") (pin "1") (pinfunction "1_1") (pintype "passive"))
      (node (ref "SW2") (pin "3") (pinfunction "P$2_3") (pintype "passive"))
      (node (ref "SW2") (pin "4") (pinfunction "P$2_4") (pintype "passive"))
    )
    (net (code "22") (name "Net-(C19-Pad2)") (class "Default")
      (node (ref "C19") (pin "2") (pinfunction "2_2") (pintype "passive"))
      (node (ref "R19") (pin "1") (pinfunction "1_1") (pintype "passive"))
      (node (ref "SW3") (pin "2") (pinfunction "2_2") (pintype "passive"))
    )
    (net (code "23") (name "Net-(C20-Pad2)") (class "Default")
      (node (ref "C20") (pin "2") (pinfunction "2_2") (pintype "passive"))
      (node (ref "R21") (pin "1") (pinfunction "1_1") (pintype "passive"))
      (node (ref "SW4") (pin "2") (pinfunction "2_2") (pintype "passive"))
    )
    (net (code "24") (name "Net-(D1-Pad2)") (class "Default")
      (node (ref "D1") (pin "2") (pinfunction "2_2") (pintype "passive"))
      (node (ref "R23") (pin "1") (pinfunction "1_1") (pintype "passive"))
    )
    (net (code "25") (name "Net-(D2-Pad1)") (class "Default")
      (node (ref "D2") (pin "1") (pinfunction "1_1") (pintype "passive"))
      (node (ref "R20") (pin "1") (pinfunction "1_1") (pintype "passive"))
    )
    (net (code "26") (name "Net-(J1-D+)") (class "Default")
      (node (ref "J1") (pin "3") (pinfunction "D+_3") (pintype "bidirectional"))
      (node (ref "U7") (pin "4") (pinfunction "D+_4") (pintype "bidirectional"))
    )
    (net (code "27") (name "Net-(J1-D-)") (class "Default")
      (node (ref "J1") (pin "2") (pinfunction "D-_2") (pintype "bidirectional"))
      (node (ref "U7") (pin "5") (pinfunction "D-_5") (pintype "bidirectional"))
    )
    (net (code "28") (name "Net-(Q1-PadB)") (class "Default")
      (node (ref "Q1") (pin "B") (pinfunction "B_B") (pintype "passive"))
      (node (ref "R17") (pin "2") (pinfunction "2_2") (pintype "passive"))
    )
    (net (code "29") (name "Net-(Q2-PadB)") (class "Default")
      (node (ref "Q2") (pin "B") (pinfunction "B_B") (pintype "passive"))
      (node (ref "R18") (pin "2") (pinfunction "2_2") (pintype "passive"))
    )
    (net (code "30") (name "Net-(Q3-PadD)") (class "Default")
      (node (ref "Q3") (pin "D") (pinfunction "D_D") (pintype "passive"))
      (node (ref "U2") (pin "F") (pinfunction "F_F") (pintype "passive"))
      (node (ref "U2") (pin "G") (pinfunction "G_G") (pintype "passive"))
    )
    (net (code "31") (name "Net-(R4-Pad1)") (class "Default")
      (node (ref "R4") (pin "1") (pinfunction "1_1") (pintype "passive"))
      (node (ref "SW1") (pin "1") (pinfunction "1_1") (pintype "passive"))
    )
    (net (code "32") (name "Net-(R25-Pad2)") (class "Default")
      (node (ref "R25") (pin "2") (pinfunction "2_2") (pintype "passive"))
      (node (ref "U2") (pin "C") (pinfunction "C_C") (pintype "passive"))
    )
    (net (code "33") (name "Net-(U1-EN2)") (class "Default")
      (node (ref "R1") (pin "1") (pinfunction "1_1") (pintype "passive"))
      (node (ref "U1") (pin "5") (pinfunction "EN2_5") (pintype "passive"))
    )
    (net (code "34") (name "Net-(U1-ILM)") (class "Default")
      (node (ref "R8") (pin "2") (pinfunction "2_2") (pintype "passive"))
      (node (ref "U1") (pin "12") (pinfunction "ILM_12") (pintype "passive"))
    )
    (net (code "35") (name "Net-(U1-ISET)") (class "Default")
      (node (ref "R22") (pin "2") (pinfunction "2_2") (pintype "passive"))
      (node (ref "U1") (pin "16") (pinfunction "ISET_16") (pintype "passive"))
    )
    (net (code "36") (name "Net-(U1-SYSOFF)") (class "Default")
      (node (ref "SW1") (pin "2") (pinfunction "2_2") (pintype "passive"))
      (node (ref "U1") (pin "15") (pinfunction "SYSOFF_15") (pintype "passive"))
    )
    (net (code "37") (name "Net-(U1-TMR)") (class "Default")
      (node (ref "R7") (pin "2") (pinfunction "2_2") (pintype "passive"))
      (node (ref "U1") (pin "14") (pinfunction "TMR_14") (pintype "passive"))
    )
    (net (code "38") (name "Net-(U1-~{CHG})") (class "Default")
      (node (ref "R23") (pin "2") (pinfunction "2_2") (pintype "passive"))
      (node (ref "U1") (pin "9") (pinfunction "~{CHG}_9") (pintype "passive"))
    )
    (net (code "39") (name "Net-(U3-EN)") (class "Default")
      (node (ref "C10") (pin "2") (pinfunction "2_2") (pintype "passive"))
      (node (ref "R9") (pin "1") (pinfunction "1_1") (pintype "passive"))
      (node (ref "U3") (pin "6") (pinfunction "EN_6") (pintype "passive"))
      (node (ref "U3") (pin "7") (pinfunction "PS/SYNC_7") (pintype "passive"))
      (node (ref "U3") (pin "8") (pinfunction "VINA_8") (pintype "passive"))
    )
    (net (code "40") (name "Net-(U3-L1)") (class "Default")
      (node (ref "L2") (pin "1") (pinfunction "1_1") (pintype "passive"))
      (node (ref "U3") (pin "4") (pinfunction "L1_4") (pintype "passive"))
    )
    (net (code "41") (name "Net-(U3-L2)") (class "Default")
      (node (ref "L2") (pin "2") (pinfunction "2_2") (pintype "passive"))
      (node (ref "U3") (pin "2") (pinfunction "L2_2") (pintype "passive"))
    )
    (net (code "42") (name "Net-(U5-EN)") (class "Default")
      (node (ref "C4") (pin "2") (pinfunction "2_2") (pintype "passive"))
      (node (ref "R2") (pin "1") (pinfunction "1_1") (pintype "passive"))
      (node (ref "U5") (pin "6") (pinfunction "EN_6") (pintype "passive"))
      (node (ref "U5") (pin "7") (pinfunction "PS/SYNC_7") (pintype "passive"))
      (node (ref "U5") (pin "8") (pinfunction "VINA_8") (pintype "passive"))
    )
    (net (code "43") (name "Net-(U5-L1)") (class "Default")
      (node (ref "L1") (pin "1") (pinfunction "1_1") (pintype "passive"))
      (node (ref "U5") (pin "4") (pinfunction "L1_4") (pintype "passive"))
    )
    (net (code "44") (name "Net-(U5-L2)") (class "Default")
      (node (ref "L1") (pin "2") (pinfunction "2_2") (pintype "passive"))
      (node (ref "U5") (pin "2") (pinfunction "L2_2") (pintype "passive"))
    )
    (net (code "45") (name "Net-(U6-VDD)") (class "Default")
      (node (ref "C6") (pin "2") (pinfunction "2_2") (pintype "passive"))
      (node (ref "U6") (pin "5") (pinfunction "VDD_5") (pintype "passive"))
    )
    (net (code "46") (name "Net-(U7-TXD)") (class "Default")
      (node (ref "R12") (pin "1") (pinfunction "1_1") (pintype "passive"))
      (node (ref "U7") (pin "26") (pinfunction "TXD_26") (pintype "passive"))
    )
    (net (code "47") (name "VBAT") (class "Default")
      (node (ref "R24") (pin "1") (pinfunction "1_1") (pintype "passive"))
      (node (ref "R4") (pin "2") (pinfunction "2_2") (pintype "passive"))
      (node (ref "U1") (pin "2") (pinfunction "BAT_2") (pintype "passive"))
      (node (ref "U1") (pin "3") (pinfunction "BAT_3") (pintype "passive"))
      (node (ref "U6") (pin "7") (pinfunction "SRN_7") (pintype "passive"))
    )
    (net (code "48") (name "VOUT") (class "Default")
      (node (ref "C1") (pin "1") (pinfunction "1_1") (pintype "passive"))
      (node (ref "C21") (pin "1") (pinfunction "1_1") (pintype "passive"))
      (node (ref "C7") (pin "1") (pinfunction "1_1") (pintype "passive"))
      (node (ref "D1") (pin "1") (pinfunction "1_1") (pintype "passive"))
      (node (ref "R1") (pin "2") (pinfunction "2_2") (pintype "passive"))
      (node (ref "R2") (pin "2") (pinfunction "2_2") (pintype "passive"))
      (node (ref "R9") (pin "2") (pinfunction "2_2") (pintype "passive"))
      (node (ref "U1") (pin "10") (pinfunction "OUT_10") (pintype "passive"))
      (node (ref "U1") (pin "11") (pinfunction "OUT_11") (pintype "passive"))
      (node (ref "U3") (pin "5") (pinfunction "VIN_5") (pintype "passive"))
      (node (ref "U5") (pin "5") (pinfunction "VIN_5") (pintype "passive"))
    )
    (net (code "49") (name "VUSB") (class "Default")
      (node (ref "C17") (pin "2") (pinfunction "2_2") (pintype "passive"))
      (node (ref "C18") (pin "2") (pinfunction "2_2") (pintype "passive"))
      (node (ref "J1") (pin "1") (pinfunction "VDD_1") (pintype "power_in"))
      (node (ref "R20") (pin "2") (pinfunction "2_2") (pintype "passive"))
      (node (ref "U1") (pin "13") (pinfunction "IN_13") (pintype "passive"))
      (node (ref "U7") (pin "8") (pinfunction "VBUS_8") (pintype "power_in"))
    )
    (net (code "50") (name "unconnected-(J1-ID-Pad4)") (class "Default")
      (node (ref "J1") (pin "4") (pinfunction "ID_4") (pintype "passive+no_connect"))
    )
    (net (code "51") (name "unconnected-(U1-~{CE}-Pad4)") (class "Default")
      (node (ref "U1") (pin "4") (pinfunction "~{CE}_4") (pintype "passive"))
    )
    (net (code "52") (name "unconnected-(U1-~{PGOOD}-Pad7)") (class "Default")
      (node (ref "U1") (pin "7") (pinfunction "~{PGOOD}_7") (pintype "passive+no_connect"))
    )
    (net (code "53") (name "unconnected-(U2-PadA)") (class "Default")
      (node (ref "U2") (pin "A") (pinfunction "A_A") (pintype "passive"))
    )
    (net (code "54") (name "unconnected-(U2-PadB)") (class "Default")
      (node (ref "U2") (pin "B") (pinfunction "B_B") (pintype "passive"))
    )
    (net (code "55") (name "unconnected-(U2-PadE)") (class "Default")
      (node (ref "U2") (pin "E") (pinfunction "E_E") (pintype "passive"))
    )
    (net (code "56") (name "unconnected-(U2-PadH)") (class "Default")
      (node (ref "U2") (pin "H") (pinfunction "H_H") (pintype "passive"))
    )
    (net (code "57") (name "unconnected-(U2-PadJ)") (class "Default")
      (node (ref "U2") (pin "J") (pinfunction "J_J") (pintype "passive"))
    )
    (net (code "58") (name "unconnected-(U2-PadK)") (class "Default")
      (node (ref "U2") (pin "K") (pinfunction "K_K") (pintype "passive"))
    )
    (net (code "59") (name "unconnected-(U6-NC-Pad4)") (class "Default")
      (node (ref "U6") (pin "4") (pinfunction "NC_4") (pintype "passive+no_connect"))
    )
    (net (code "60") (name "unconnected-(U6-NC-Pad9)") (class "Default")
      (node (ref "U6") (pin "9") (pinfunction "NC_9") (pintype "passive+no_connect"))
    )
    (net (code "61") (name "unconnected-(U6-NC-Pad11)") (class "Default")
      (node (ref "U6") (pin "11") (pinfunction "NC_11") (pintype "passive+no_connect"))
    )
    (net (code "62") (name "unconnected-(U7-DCD-Pad1)") (class "Default")
      (node (ref "U7") (pin "1") (pinfunction "DCD_1") (pintype "input+no_connect"))
    )
    (net (code "63") (name "unconnected-(U7-DSR-Pad27)") (class "Default")
      (node (ref "U7") (pin "27") (pinfunction "DSR_27") (pintype "input+no_connect"))
    )
    (net (code "64") (name "unconnected-(U7-NC1-Pad10)") (class "Default")
      (node (ref "U7") (pin "10") (pinfunction "NC1_10") (pintype "passive+no_connect"))
    )
    (net (code "65") (name "unconnected-(U7-NC2-Pad13)") (class "Default")
      (node (ref "U7") (pin "13") (pinfunction "NC2_13") (pintype "passive+no_connect"))
    )
    (net (code "66") (name "unconnected-(U7-NC3-Pad14)") (class "Default")
      (node (ref "U7") (pin "14") (pinfunction "NC3_14") (pintype "passive+no_connect"))
    )
    (net (code "67") (name "unconnected-(U7-NC4-Pad15)") (class "Default")
      (node (ref "U7") (pin "15") (pinfunction "NC4_15") (pintype "passive+no_connect"))
    )
    (net (code "68") (name "unconnected-(U7-NC5-Pad16)") (class "Default")
      (node (ref "U7") (pin "16") (pinfunction "NC5_16") (pintype "passive+no_connect"))
    )
    (net (code "69") (name "unconnected-(U7-NC6-Pad17)") (class "Default")
      (node (ref "U7") (pin "17") (pinfunction "NC6_17") (pintype "passive+no_connect"))
    )
    (net (code "70") (name "unconnected-(U7-NC7-Pad18)") (class "Default")
      (node (ref "U7") (pin "18") (pinfunction "NC7_18") (pintype "passive+no_connect"))
    )
    (net (code "71") (name "unconnected-(U7-NC8-Pad19)") (class "Default")
      (node (ref "U7") (pin "19") (pinfunction "NC8_19") (pintype "passive+no_connect"))
    )
    (net (code "72") (name "unconnected-(U7-NC9-Pad20)") (class "Default")
      (node (ref "U7") (pin "20") (pinfunction "NC9_20") (pintype "passive+no_connect"))
    )
    (net (code "73") (name "unconnected-(U7-NC10-Pad21)") (class "Default")
      (node (ref "U7") (pin "21") (pinfunction "NC10_21") (pintype "passive+no_connect"))
    )
    (net (code "74") (name "unconnected-(U7-NC11-Pad22)") (class "Default")
      (node (ref "U7") (pin "22") (pinfunction "NC11_22") (pintype "passive+no_connect"))
    )
    (net (code "75") (name "unconnected-(U7-RI-Pad2)") (class "Default")
      (node (ref "U7") (pin "2") (pinfunction "RI_2") (pintype "input+no_connect"))
    )
    (net (code "76") (name "unconnected-(U7-SUSPEND-Pad12)") (class "Default")
      (node (ref "U7") (pin "12") (pinfunction "SUSPEND_12") (pintype "passive+no_connect"))
    )
    (net (code "77") (name "unconnected-(U7-~{RST}-Pad9)") (class "Default")
      (node (ref "U7") (pin "9") (pinfunction "~{RST}_9") (pintype "input+no_connect"))
    )
    (net (code "78") (name "unconnected-(U7-~{SUSPEND}-Pad11)") (class "Default")
      (node (ref "U7") (pin "11") (pinfunction "~{SUSPEND}_11") (pintype "passive+no_connect"))
    )
    (net (code "79") (name "unconnected-(U8-CLK-Pad20)") (class "Default")
      (node (ref "U8") (pin "20") (pinfunction "CLK_20") (pintype "passive"))
    )
    (net (code "80") (name "unconnected-(U8-CMD-Pad19)") (class "Default")
      (node (ref "U8") (pin "19") (pinfunction "CMD_19") (pintype "passive"))
    )
    (net (code "81") (name "unconnected-(U8-IO12-Pad14)") (class "Default")
      (node (ref "U8") (pin "14") (pinfunction "IO12_14") (pintype "bidirectional"))
    )
    (net (code "82") (name "unconnected-(U8-IO13-Pad16)") (class "Default")
      (node (ref "U8") (pin "16") (pinfunction "IO13_16") (pintype "bidirectional"))
    )
    (net (code "83") (name "unconnected-(U8-IO14-Pad13)") (class "Default")
      (node (ref "U8") (pin "13") (pinfunction "IO14_13") (pintype "bidirectional"))
    )
    (net (code "84") (name "unconnected-(U8-IO15-Pad23)") (class "Default")
      (node (ref "U8") (pin "23") (pinfunction "IO15_23") (pintype "bidirectional"))
    )
    (net (code "85") (name "unconnected-(U8-IO16-Pad27)") (class "Default")
      (node (ref "U8") (pin "27") (pinfunction "IO16_27") (pintype "bidirectional"))
    )
    (net (code "86") (name "unconnected-(U8-IO19-Pad31)") (class "Default")
      (node (ref "U8") (pin "31") (pinfunction "IO19_31") (pintype "bidirectional"))
    )
    (net (code "87") (name "unconnected-(U8-IO20-Pad32)") (class "Default")
      (node (ref "U8") (pin "32") (pinfunction "IO20_32") (pintype "bidirectional"))
    )
    (net (code "88") (name "unconnected-(U8-IO23-Pad37)") (class "Default")
      (node (ref "U8") (pin "37") (pinfunction "IO23_37") (pintype "bidirectional"))
    )
    (net (code "89") (name "unconnected-(U8-IO25-Pad10)") (class "Default")
      (node (ref "U8") (pin "10") (pinfunction "IO25_10") (pintype "bidirectional"))
    )
    (net (code "90") (name "unconnected-(U8-IO26-Pad11)") (class "Default")
      (node (ref "U8") (pin "11") (pinfunction "IO26_11") (pintype "bidirectional"))
    )
    (net (code "91") (name "unconnected-(U8-IO27-Pad12)") (class "Default")
      (node (ref "U8") (pin "12") (pinfunction "IO27_12") (pintype "bidirectional"))
    )
    (net (code "92") (name "unconnected-(U8-IO32-Pad8)") (class "Default")
      (node (ref "U8") (pin "8") (pinfunction "IO32_8") (pintype "bidirectional"))
    )
    (net (code "93") (name "unconnected-(U8-IO33-Pad9)") (class "Default")
      (node (ref "U8") (pin "9") (pinfunction "IO33_9") (pintype "bidirectional"))
    )
    (net (code "94") (name "unconnected-(U8-IO34-Pad6)") (class "Default")
      (node (ref "U8") (pin "6") (pinfunction "IO34_6") (pintype "bidirectional"))
    )
    (net (code "95") (name "unconnected-(U8-IO35-Pad7)") (class "Default")
      (node (ref "U8") (pin "7") (pinfunction "IO35_7") (pintype "bidirectional"))
    )
    (net (code "96") (name "unconnected-(U8-SD0-Pad21)") (class "Default")
      (node (ref "U8") (pin "21") (pinfunction "SD0_21") (pintype "passive"))
    )
    (net (code "97") (name "unconnected-(U8-SD1-Pad22)") (class "Default")
      (node (ref "U8") (pin "22") (pinfunction "SD1_22") (pintype "passive"))
    )
    (net (code "98") (name "unconnected-(U8-SD2-Pad17)") (class "Default")
      (node (ref "U8") (pin "17") (pinfunction "SD2_17") (pintype "passive"))
    )
    (net (code "99") (name "unconnected-(U8-SD3-Pad18)") (class "Default")
      (node (ref "U8") (pin "18") (pinfunction "SD3_18") (pintype "passive"))
    )
    (net (code "100") (name "unconnected-(U8-SVN-Pad5)") (class "Default")
      (node (ref "U8") (pin "5") (pinfunction "SVN_5") (pintype "passive"))
    )
    (net (code "101") (name "unconnected-(U8-SVP-Pad4)") (class "Default")
      (node (ref "U8") (pin "4") (pinfunction "SVP_4") (pintype "passive"))
    )
  )
)
